# Output.net
KiCad netlist of a schematic drawn in Altium Designer
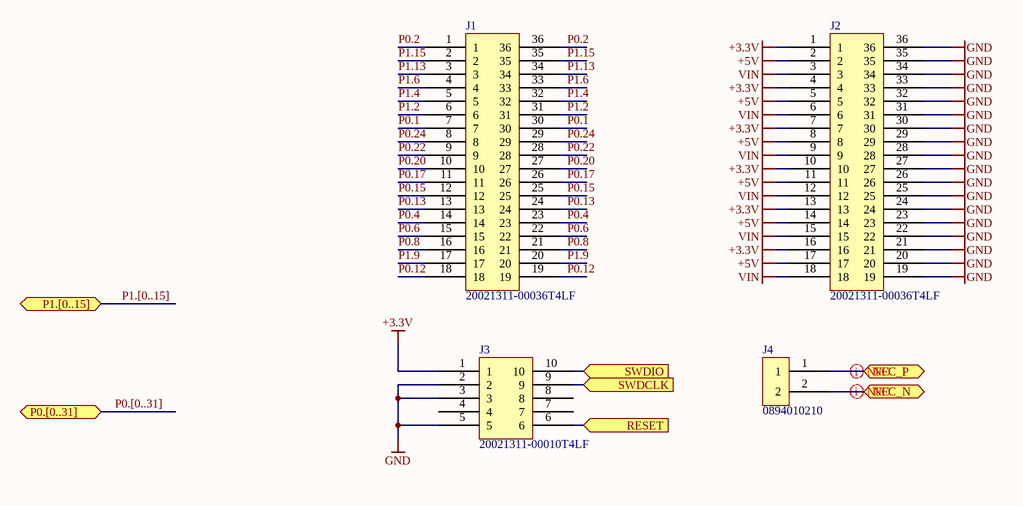
[diagram p0: Output.SchDoc]

(export (version "E")
  (design (tool "Eeschema 10.0.6"))
  (components
    (comp (ref "J1")
      (value "20021311-00036T4LF")
      (footprint "DIP36")
      (description "36 Position Receptacle Connector 0.050\" (1.27mm) Through Hole Gold")
      (fields (field (name "MANUFACTURER") "Amphenol FCI") (field (name "CHECKED") "false"))
      (libsource (lib "Componentes") (part "20021311-00036T4LF"))
    )
    (comp (ref "J2")
      (value "20021311-00036T4LF")
      (footprint "DIP36")
      (description "36 Position Receptacle Connector 0.050\" (1.27mm) Through Hole Gold")
      (fields (field (name "MANUFACTURER") "Amphenol FCI") (field (name "CHECKED") "false"))
      (libsource (lib "Componentes") (part "20021311-00036T4LF"))
    )
    (comp (ref "J3")
      (value "20021311-00010T4LF")
      (footprint "DIP10")
      (description "10 Position Receptacle Connector 0.050\" (1.27mm) Through Hole Gold")
      (fields (field (name "MANUFACTURER") "Amphenol FCI") (field (name "CHECKED") "False"))
      (libsource (lib "Componentes") (part "20021311-00010T4LF"))
    )
    (comp (ref "J4")
      (value "0894010210")
      (footprint "DIP2")
      (description "Conn Shrouded Header HDR 2 POS 2mm Solder RA Thru-Hole Bag")
      (fields (field (name "MANUFACTURER") "Molex") (field (name "CHECKED") "False"))
      (libsource (lib "Componentes") (part "0894010210"))
    )
  )
  (nets
    (net (code "31") (name "+3.3V") (class "Default")
      (node (ref "J2") (pin "1") (pinfunction "1_1") (pintype "passive"))
      (node (ref "J2") (pin "10") (pinfunction "10_10") (pintype "passive"))
      (node (ref "J2") (pin "13") (pinfunction "13_13") (pintype "passive"))
      (node (ref "J2") (pin "16") (pinfunction "16_16") (pintype "passive"))
      (node (ref "J2") (pin "4") (pinfunction "4_4") (pintype "passive"))
      (node (ref "J2") (pin "7") (pinfunction "7_7") (pintype "passive"))
      (node (ref "J3") (pin "1") (pinfunction "1_1") (pintype "power_in"))
    )
    (net (code "32") (name "+5V") (class "Default")
      (node (ref "J2") (pin "11") (pinfunction "11_11") (pintype "passive"))
      (node (ref "J2") (pin "14") (pinfunction "14_14") (pintype "passive"))
      (node (ref "J2") (pin "17") (pinfunction "17_17") (pintype "passive"))
      (node (ref "J2") (pin "2") (pinfunction "2_2") (pintype "passive"))
      (node (ref "J2") (pin "5") (pinfunction "5_5") (pintype "passive"))
      (node (ref "J2") (pin "8") (pinfunction "8_8") (pintype "passive"))
    )
    (net (code "33") (name "/NFC_N") (class "Default")
      (node (ref "J4") (pin "2") (pinfunction "2_2") (pintype "power_in"))
    )
    (net (code "34") (name "/NFC_P") (class "Default")
      (node (ref "J4") (pin "1") (pinfunction "1_1") (pintype "power_in"))
    )
    (net (code "35") (name "/P0.1") (class "Default")
      (node (ref "J1") (pin "30") (pinfunction "30_30") (pintype "passive"))
      (node (ref "J1") (pin "7") (pinfunction "7_7") (pintype "passive"))
    )
    (net (code "36") (name "/P0.2") (class "Default")
      (node (ref "J1") (pin "1") (pinfunction "1_1") (pintype "passive"))
      (node (ref "J1") (pin "36") (pinfunction "36_36") (pintype "passive"))
    )
    (net (code "37") (name "/P0.4") (class "Default")
      (node (ref "J1") (pin "14") (pinfunction "14_14") (pintype "passive"))
      (node (ref "J1") (pin "23") (pinfunction "23_23") (pintype "passive"))
    )
    (net (code "38") (name "/P0.6") (class "Default")
      (node (ref "J1") (pin "15") (pinfunction "15_15") (pintype "passive"))
      (node (ref "J1") (pin "22") (pinfunction "22_22") (pintype "passive"))
    )
    (net (code "39") (name "/P0.8") (class "Default")
      (node (ref "J1") (pin "16") (pinfunction "16_16") (pintype "passive"))
      (node (ref "J1") (pin "21") (pinfunction "21_21") (pintype "passive"))
    )
    (net (code "40") (name "/P0.12") (class "Default")
      (node (ref "J1") (pin "18") (pinfunction "18_18") (pintype "passive"))
      (node (ref "J1") (pin "19") (pinfunction "19_19") (pintype "passive"))
    )
    (net (code "41") (name "/P0.13") (class "Default")
      (node (ref "J1") (pin "13") (pinfunction "13_13") (pintype "passive"))
      (node (ref "J1") (pin "24") (pinfunction "24_24") (pintype "passive"))
    )
    (net (code "42") (name "/P0.15") (class "Default")
      (node (ref "J1") (pin "12") (pinfunction "12_12") (pintype "passive"))
      (node (ref "J1") (pin "25") (pinfunction "25_25") (pintype "passive"))
    )
    (net (code "43") (name "/P0.17") (class "Default")
      (node (ref "J1") (pin "11") (pinfunction "11_11") (pintype "passive"))
      (node (ref "J1") (pin "26") (pinfunction "26_26") (pintype "passive"))
    )
    (net (code "44") (name "/P0.20") (class "Default")
      (node (ref "J1") (pin "10") (pinfunction "10_10") (pintype "passive"))
      (node (ref "J1") (pin "27") (pinfunction "27_27") (pintype "passive"))
    )
    (net (code "45") (name "/P0.22") (class "Default")
      (node (ref "J1") (pin "28") (pinfunction "28_28") (pintype "passive"))
      (node (ref "J1") (pin "9") (pinfunction "9_9") (pintype "passive"))
    )
    (net (code "46") (name "/P0.24") (class "Default")
      (node (ref "J1") (pin "29") (pinfunction "29_29") (pintype "passive"))
      (node (ref "J1") (pin "8") (pinfunction "8_8") (pintype "passive"))
    )
    (net (code "48") (name "/P1.2") (class "Default")
      (node (ref "J1") (pin "31") (pinfunction "31_31") (pintype "passive"))
      (node (ref "J1") (pin "6") (pinfunction "6_6") (pintype "passive"))
    )
    (net (code "49") (name "/P1.4") (class "Default")
      (node (ref "J1") (pin "32") (pinfunction "32_32") (pintype "passive"))
      (node (ref "J1") (pin "5") (pinfunction "5_5") (pintype "passive"))
    )
    (net (code "50") (name "/P1.6") (class "Default")
      (node (ref "J1") (pin "33") (pinfunction "33_33") (pintype "passive"))
      (node (ref "J1") (pin "4") (pinfunction "4_4") (pintype "passive"))
    )
    (net (code "51") (name "/P1.9") (class "Default")
      (node (ref "J1") (pin "17") (pinfunction "17_17") (pintype "passive"))
      (node (ref "J1") (pin "20") (pinfunction "20_20") (pintype "passive"))
    )
    (net (code "52") (name "/P1.13") (class "Default")
      (node (ref "J1") (pin "3") (pinfunction "3_3") (pintype "passive"))
      (node (ref "J1") (pin "34") (pinfunction "34_34") (pintype "passive"))
    )
    (net (code "53") (name "/P1.15") (class "Default")
      (node (ref "J1") (pin "2") (pinfunction "2_2") (pintype "passive"))
      (node (ref "J1") (pin "35") (pinfunction "35_35") (pintype "passive"))
    )
    (net (code "55") (name "/RESET") (class "Default")
      (node (ref "J3") (pin "6") (pinfunction "6_6") (pintype "power_in"))
    )
    (net (code "56") (name "/SWDCLK") (class "Default")
      (node (ref "J3") (pin "9") (pinfunction "9_9") (pintype "power_in"))
    )
    (net (code "57") (name "/SWDIO") (class "Default")
      (node (ref "J3") (pin "10") (pinfunction "10_10") (pintype "power_in"))
    )
    (net (code "58") (name "GND") (class "Default")
      (node (ref "J2") (pin "19") (pinfunction "19_19") (pintype "passive"))
      (node (ref "J2") (pin "20") (pinfunction "20_20") (pintype "passive"))
      (node (ref "J2") (pin "21") (pinfunction "21_21") (pintype "passive"))
      (node (ref "J2") (pin "22") (pinfunction "22_22") (pintype "passive"))
      (node (ref "J2") (pin "23") (pinfunction "23_23") (pintype "passive"))
      (node (ref "J2") (pin "24") (pinfunction "24_24") (pintype "passive"))
      (node (ref "J2") (pin "25") (pinfunction "25_25") (pintype "passive"))
      (node (ref "J2") (pin "26") (pinfunction "26_26") (pintype "passive"))
      (node (ref "J2") (pin "27") (pinfunction "27_27") (pintype "passive"))
      (node (ref "J2") (pin "28") (pinfunction "28_28") (pintype "passive"))
      (node (ref "J2") (pin "29") (pinfunction "29_29") (pintype "passive"))
      (node (ref "J2") (pin "30") (pinfunction "30_30") (pintype "passive"))
      (node (ref "J2") (pin "31") (pinfunction "31_31") (pintype "passive"))
      (node (ref "J2") (pin "32") (pinfunction "32_32") (pintype "passive"))
      (node (ref "J2") (pin "33") (pinfunction "33_33") (pintype "passive"))
      (node (ref "J2") (pin "34") (pinfunction "34_34") (pintype "passive"))
      (node (ref "J2") (pin "35") (pinfunction "35_35") (pintype "passive"))
      (node (ref "J2") (pin "36") (pinfunction "36_36") (pintype "passive"))
      (node (ref "J3") (pin "2") (pinfunction "2_2") (pintype "power_in"))
      (node (ref "J3") (pin "3") (pinfunction "3_3") (pintype "power_in"))
      (node (ref "J3") (pin "5") (pinfunction "5_5") (pintype "power_in"))
    )
    (net (code "59") (name "VIN") (class "Default")
      (node (ref "J2") (pin "12") (pinfunction "12_12") (pintype "passive"))
      (node (ref "J2") (pin "15") (pinfunction "15_15") (pintype "passive"))
      (node (ref "J2") (pin "18") (pinfunction "18_18") (pintype "passive"))
      (node (ref "J2") (pin "3") (pinfunction "3_3") (pintype "passive"))
      (node (ref "J2") (pin "6") (pinfunction "6_6") (pintype "passive"))
      (node (ref "J2") (pin "9") (pinfunction "9_9") (pintype "passive"))
    )
    (net (code "60") (name "unconnected-(J3-Pad4)") (class "Default")
      (node (ref "J3") (pin "4") (pinfunction "4_4") (pintype "power_in"))
    )
    (net (code "61") (name "unconnected-(J3-Pad7)") (class "Default")
      (node (ref "J3") (pin "7") (pinfunction "7_7") (pintype "power_in"))
    )
    (net (code "62") (name "unconnected-(J3-Pad8)") (class "Default")
      (node (ref "J3") (pin "8") (pinfunction "8_8") (pintype "power_in"))
    )
  )
)
